# rgb-led-cc-driver-mk-1_0.net
KiCad netlist of a schematic drawn in EAGLE
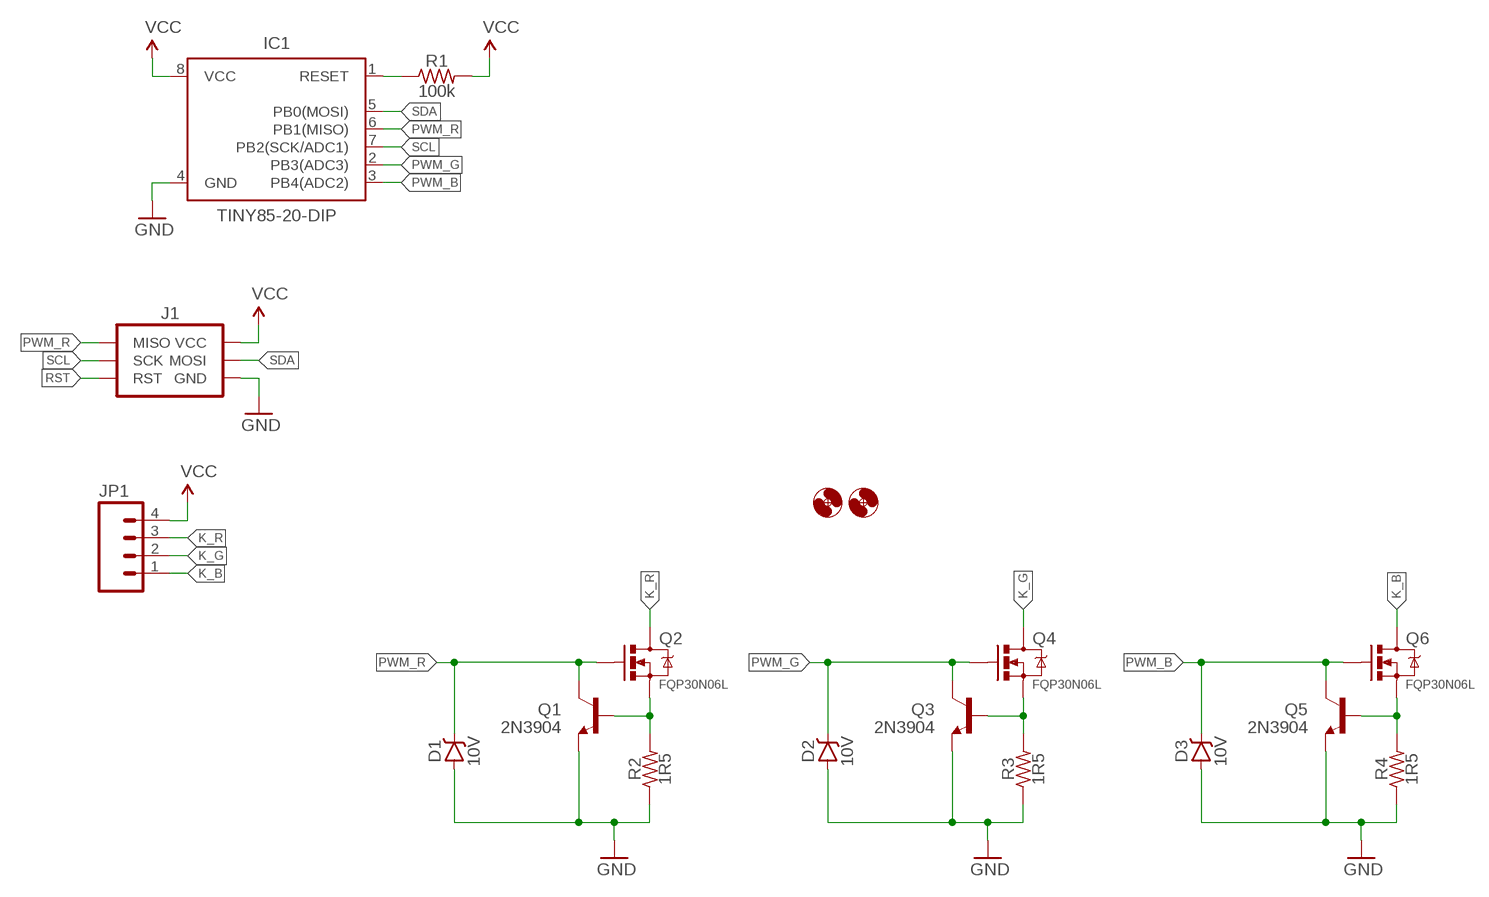
[diagram p0: schematic, sheet 1]

(export (version "E")
  (design (tool "Eeschema 10.0.6"))
  (components
    (comp (ref "D1")
      (value "10V")
      (footprint "eagle-import:DIODE-ZENNER-10.16MM")
      (libsource (lib "eagle-import") (part "DIODE-ZENER10.16MM-PTH"))
    )
    (comp (ref "D2")
      (value "10V")
      (footprint "eagle-import:DIODE-ZENNER-10.16MM")
      (libsource (lib "eagle-import") (part "DIODE-ZENER10.16MM-PTH"))
    )
    (comp (ref "D3")
      (value "10V")
      (footprint "eagle-import:DIODE-ZENNER-10.16MM")
      (libsource (lib "eagle-import") (part "DIODE-ZENER10.16MM-PTH"))
    )
    (comp (ref "H1")
      (value "HOLE#2")
      (footprint "eagle-import:HOLE-#2")
      (libsource (lib "eagle-import") (part "HOLE#2"))
    )
    (comp (ref "H2")
      (value "HOLE#2")
      (footprint "eagle-import:HOLE-#2")
      (libsource (lib "eagle-import") (part "HOLE#2"))
    )
    (comp (ref "IC1")
      (value "TINY85-20-DIP")
      (footprint "eagle-import:DIP08")
      (libsource (lib "eagle-import") (part "ATTINY45TINY85-20-DIP"))
    )
    (comp (ref "J1")
      (value "AVR_SPI_PRG_6PTH_INLINE_I2C")
      (footprint "eagle-import:AVR_ISP_INLINE_PTH_I2C")
      (libsource (lib "eagle-import") (part "AVR_SPI_PRG_6PTH_INLINE_I2C"))
    )
    (comp (ref "JP1")
      (value "M04PTH")
      (footprint "eagle-import:1X04-PTH-VERT")
      (libsource (lib "eagle-import") (part "M04PTH"))
    )
    (comp (ref "Q1")
      (value "2N3904")
      (footprint "eagle-import:TO-92-AMMO")
      (libsource (lib "eagle-import") (part "TRANSISTOR_NPNTO-92-AMMO-EBC"))
    )
    (comp (ref "Q2")
      (value "FQP30N06L")
      (footprint "eagle-import:TO220-THERMPAD")
      (libsource (lib "eagle-import") (part "MOSFET-NCHANNELTO-220"))
    )
    (comp (ref "Q3")
      (value "2N3904")
      (footprint "eagle-import:TO-92-AMMO")
      (libsource (lib "eagle-import") (part "TRANSISTOR_NPNTO-92-AMMO-EBC"))
    )
    (comp (ref "Q4")
      (value "FQP30N06L")
      (footprint "eagle-import:TO220-THERMPAD")
      (libsource (lib "eagle-import") (part "MOSFET-NCHANNELTO-220"))
    )
    (comp (ref "Q5")
      (value "2N3904")
      (footprint "eagle-import:TO-92-AMMO")
      (libsource (lib "eagle-import") (part "TRANSISTOR_NPNTO-92-AMMO-EBC"))
    )
    (comp (ref "Q6")
      (value "FQP30N06L")
      (footprint "eagle-import:TO220-THERMPAD")
      (libsource (lib "eagle-import") (part "MOSFET-NCHANNELTO-220"))
    )
    (comp (ref "R1")
      (value "100k")
      (footprint "eagle-import:RESISTOR-AXIAL-PTH-10.16MM")
      (libsource (lib "eagle-import") (part "RESISTORPTH-AXIAL-10.16MM"))
    )
    (comp (ref "R2")
      (value "1R5")
      (footprint "eagle-import:RESISTOR-AXIAL-PTH-10.16MM")
      (libsource (lib "eagle-import") (part "RESISTORPTH-AXIAL-10.16MM"))
    )
    (comp (ref "R3")
      (value "1R5")
      (footprint "eagle-import:RESISTOR-AXIAL-PTH-10.16MM")
      (libsource (lib "eagle-import") (part "RESISTORPTH-AXIAL-10.16MM"))
    )
    (comp (ref "R4")
      (value "1R5")
      (footprint "eagle-import:RESISTOR-AXIAL-PTH-10.16MM")
      (libsource (lib "eagle-import") (part "RESISTORPTH-AXIAL-10.16MM"))
    )
  )
  (nets
    (net (code "1") (name "GND") (class "Default")
      (node (ref "D1") (pin "A") (pinfunction "A_A") (pintype "passive"))
      (node (ref "D2") (pin "A") (pinfunction "A_A") (pintype "passive"))
      (node (ref "D3") (pin "A") (pinfunction "A_A") (pintype "passive"))
      (node (ref "IC1") (pin "4") (pinfunction "GND_4") (pintype "bidirectional"))
      (node (ref "J1") (pin "GND") (pinfunction "GND_GND") (pintype "passive"))
      (node (ref "Q1") (pin "1") (pinfunction "E_1") (pintype "passive"))
      (node (ref "Q3") (pin "1") (pinfunction "E_1") (pintype "passive"))
      (node (ref "Q5") (pin "1") (pinfunction "E_1") (pintype "passive"))
      (node (ref "R2") (pin "P$1") (pinfunction "1_P$1") (pintype "passive"))
      (node (ref "R3") (pin "P$1") (pinfunction "1_P$1") (pintype "passive"))
      (node (ref "R4") (pin "P$1") (pinfunction "1_P$1") (pintype "passive"))
    )
    (net (code "2") (name "K_B") (class "Default")
      (node (ref "JP1") (pin "1") (pinfunction "1_1") (pintype "passive"))
      (node (ref "Q6") (pin "2@1") (pinfunction "D_2@1") (pintype "passive"))
      (node (ref "Q6") (pin "2@2") (pinfunction "D_2@2") (pintype "passive"))
    )
    (net (code "3") (name "K_G") (class "Default")
      (node (ref "JP1") (pin "2") (pinfunction "2_2") (pintype "passive"))
      (node (ref "Q4") (pin "2@1") (pinfunction "D_2@1") (pintype "passive"))
      (node (ref "Q4") (pin "2@2") (pinfunction "D_2@2") (pintype "passive"))
    )
    (net (code "4") (name "K_R") (class "Default")
      (node (ref "JP1") (pin "3") (pinfunction "3_3") (pintype "passive"))
      (node (ref "Q2") (pin "2@1") (pinfunction "D_2@1") (pintype "passive"))
      (node (ref "Q2") (pin "2@2") (pinfunction "D_2@2") (pintype "passive"))
    )
    (net (code "5") (name "Net-(Q1-B)") (class "Default")
      (node (ref "Q1") (pin "2") (pinfunction "B_2") (pintype "passive"))
      (node (ref "Q2") (pin "3") (pinfunction "S_3") (pintype "passive"))
      (node (ref "R2") (pin "P$2") (pinfunction "2_P$2") (pintype "passive"))
    )
    (net (code "6") (name "Net-(Q3-B)") (class "Default")
      (node (ref "Q3") (pin "2") (pinfunction "B_2") (pintype "passive"))
      (node (ref "Q4") (pin "3") (pinfunction "S_3") (pintype "passive"))
      (node (ref "R3") (pin "P$2") (pinfunction "2_P$2") (pintype "passive"))
    )
    (net (code "7") (name "Net-(Q5-B)") (class "Default")
      (node (ref "Q5") (pin "2") (pinfunction "B_2") (pintype "passive"))
      (node (ref "Q6") (pin "3") (pinfunction "S_3") (pintype "passive"))
      (node (ref "R4") (pin "P$2") (pinfunction "2_P$2") (pintype "passive"))
    )
    (net (code "8") (name "PWM_B") (class "Default")
      (node (ref "D3") (pin "K") (pinfunction "C_K") (pintype "passive"))
      (node (ref "IC1") (pin "3") (pinfunction "PB4(ADC2)_3") (pintype "bidirectional"))
      (node (ref "Q5") (pin "3") (pinfunction "C_3") (pintype "passive"))
      (node (ref "Q6") (pin "1") (pinfunction "G_1") (pintype "passive"))
    )
    (net (code "9") (name "PWM_G") (class "Default")
      (node (ref "D2") (pin "K") (pinfunction "C_K") (pintype "passive"))
      (node (ref "IC1") (pin "2") (pinfunction "PB3(ADC3)_2") (pintype "bidirectional"))
      (node (ref "Q3") (pin "3") (pinfunction "C_3") (pintype "passive"))
      (node (ref "Q4") (pin "1") (pinfunction "G_1") (pintype "passive"))
    )
    (net (code "10") (name "PWM_R") (class "Default")
      (node (ref "D1") (pin "K") (pinfunction "C_K") (pintype "passive"))
      (node (ref "IC1") (pin "6") (pinfunction "PB1(MISO)_6") (pintype "bidirectional"))
      (node (ref "J1") (pin "MISO") (pinfunction "MISO_MISO") (pintype "passive"))
      (node (ref "Q1") (pin "3") (pinfunction "C_3") (pintype "passive"))
      (node (ref "Q2") (pin "1") (pinfunction "G_1") (pintype "passive"))
    )
    (net (code "11") (name "RST") (class "Default")
      (node (ref "IC1") (pin "1") (pinfunction "RESET_1") (pintype "bidirectional"))
      (node (ref "J1") (pin "RESET") (pinfunction "RST_RESET") (pintype "passive"))
      (node (ref "R1") (pin "P$1") (pinfunction "1_P$1") (pintype "passive"))
    )
    (net (code "12") (name "SCL") (class "Default")
      (node (ref "IC1") (pin "7") (pinfunction "PB2(SCK/ADC1)_7") (pintype "bidirectional"))
      (node (ref "J1") (pin "SCK") (pinfunction "SCK_SCK") (pintype "passive"))
    )
    (net (code "13") (name "SDA") (class "Default")
      (node (ref "IC1") (pin "5") (pinfunction "PB0(MOSI)_5") (pintype "bidirectional"))
      (node (ref "J1") (pin "MOSI") (pinfunction "MOSI_MOSI") (pintype "passive"))
    )
    (net (code "14") (name "VCC") (class "Default")
      (node (ref "IC1") (pin "8") (pinfunction "VCC_8") (pintype "bidirectional"))
      (node (ref "J1") (pin "VCC") (pinfunction "VCC_VCC") (pintype "passive"))
      (node (ref "JP1") (pin "4") (pinfunction "4_4") (pintype "passive"))
      (node (ref "R1") (pin "P$2") (pinfunction "2_P$2") (pintype "passive"))
    )
  )
)
